# Solar_Batter_Charger_SCH_1.net
KiCad netlist of a schematic drawn in Altium Designer
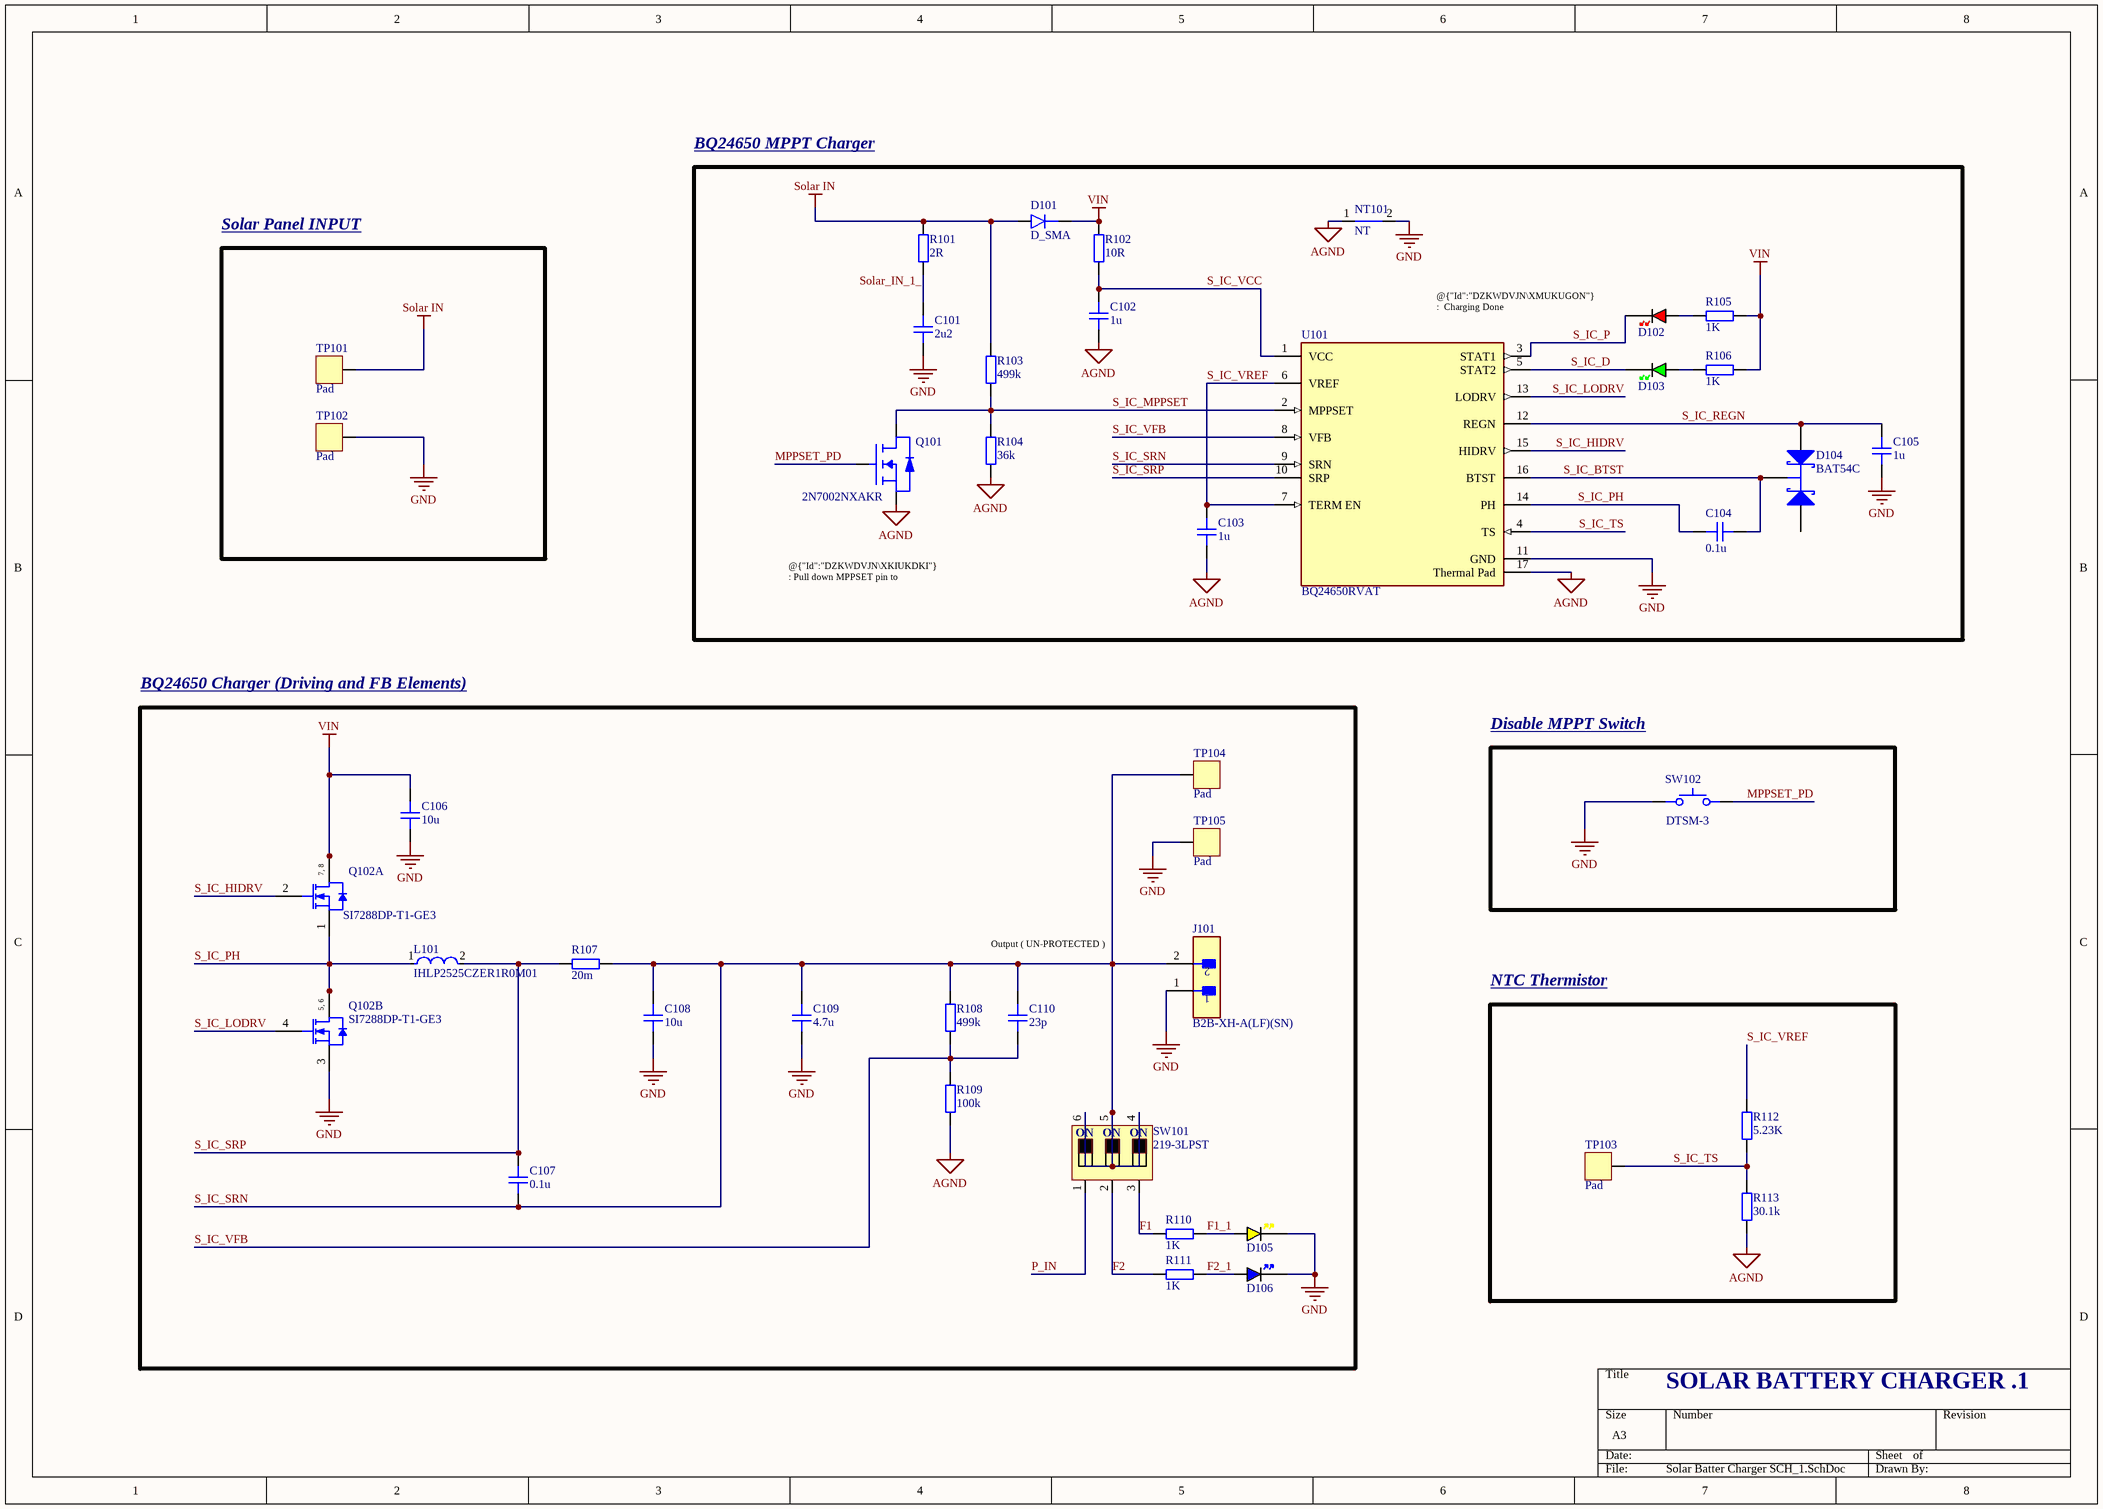
[diagram p0: Solar Batter Charger SCH_1.SchDoc]

(export (version "E")
  (design (tool "Eeschema 10.0.6"))
  (components
    (comp (ref "C101")
      (value "2u2")
      (footprint "CAP_1210")
      (description "Capacitor SMD 1210")
      (libsource (lib "Schematic-Lib-PhilsLab") (part "CAP_1210"))
    )
    (comp (ref "C102")
      (value "1u")
      (footprint "CAP_0805")
      (description "Capacitor SMD 0805")
      (libsource (lib "Schematic-Lib-PhilsLab") (part "CAP_0805"))
    )
    (comp (ref "C103")
      (value "1u")
      (footprint "CAP_0402")
      (description "Capacitor SMD 0402")
      (libsource (lib "Schematic-Lib-PhilsLab") (part "CAP_0402"))
    )
    (comp (ref "C104")
      (value "0.1u")
      (footprint "CAP_0805")
      (description "Capacitor SMD 0805")
      (libsource (lib "Schematic-Lib-PhilsLab") (part "CAP_0805"))
    )
    (comp (ref "C105")
      (value "1u")
      (footprint "CAP_0805")
      (description "Capacitor SMD 0805")
      (libsource (lib "Schematic-Lib-PhilsLab") (part "CAP_0805"))
    )
    (comp (ref "C106")
      (value "10u")
      (footprint "CAP_1210")
      (description "Capacitor SMD 1210")
      (libsource (lib "Schematic-Lib-PhilsLab") (part "CAP_1210"))
    )
    (comp (ref "C107")
      (value "0.1u")
      (footprint "CAP_0805")
      (description "Capacitor SMD 0805")
      (libsource (lib "Schematic-Lib-PhilsLab") (part "CAP_0805"))
    )
    (comp (ref "C108")
      (value "10u")
      (footprint "CAP_1210")
      (description "Capacitor SMD 1210")
      (libsource (lib "Schematic-Lib-PhilsLab") (part "CAP_1210"))
    )
    (comp (ref "C109")
      (value "4.7u")
      (footprint "CAP_1210")
      (description "Capacitor SMD 1210")
      (libsource (lib "Schematic-Lib-PhilsLab") (part "CAP_1210"))
    )
    (comp (ref "C110")
      (value "23p")
      (footprint "CAP_0603")
      (description "Capacitor SMD 0603")
      (libsource (lib "Schematic-Lib-PhilsLab") (part "CAP_0603"))
    )
    (comp (ref "D101")
      (value "D_SMA")
      (footprint "DO-214AC-2 (SMA)")
      (description "Diode SMD SMA (DO-214AA)")
      (libsource (lib "Schematic-Lib-PhilsLab") (part "D_SMA"))
    )
    (comp (ref "D102")
      (value "RED")
      (footprint "LED_0402_RED")
      (description "LED 0402 RED SMD")
      (libsource (lib "Schematic-Lib-PhilsLab") (part "LED_0402_RED"))
    )
    (comp (ref "D103")
      (value "GREEN")
      (footprint "LED_0402_GREEN")
      (description "LED 0402 GREEN SMD")
      (libsource (lib "Schematic-Lib-PhilsLab") (part "LED_0402_GREEN"))
    )
    (comp (ref "D104")
      (value "BAT54C")
      (footprint "NXP-SOT23-3_V")
      (description "Schottky Barrier Diode, 30 V, 2 uA, -55 to 150 degC, 3-Pin SOT23, RoHS, Tape and Reel")
      (fields (field (name "MANUFACTURER") "NXP Semiconductors"))
      (libsource (lib "Altium Content Vault") (part "NXP-DSKY_A1A2K3-3"))
    )
    (comp (ref "D105")
      (value "YELLOW")
      (footprint "LED_0603_YELLOW")
      (description "LED 0603 YELLOW SMD")
      (libsource (lib "Schematic-Lib-PhilsLab") (part "LED_0603_YELLOW"))
    )
    (comp (ref "D106")
      (value "BLUE")
      (footprint "LED_0603_BLUE")
      (description "LED 0603 BLUE SMD")
      (libsource (lib "Schematic-Lib-PhilsLab") (part "LED_0603_BLUE"))
    )
    (comp (ref "J101")
      (value "B2B-XH-A(LF)(SN)")
      (footprint "FP-B2B-XH-A_LF_SN-MFG")
      (description "CONN HEADER VERT 2POS 2.5MM")
      (libsource (lib "Altium Content Vault") (part "3bc925449376181038e59eaffc5286c"))
    )
    (comp (ref "L101")
      (value "IHLP2525CZER1R0M01")
      (footprint "FP-IHLP-2525CZ-FP_2_413x3-MFG")
      (description "Commercial Inductors, High Saturation Series 1uH 11A 10mΩ 20%")
      (fields (field (name "TOLERANCE") "20%"))
      (libsource (lib "Altium Content Vault") (part "725321dda6339637d4d059423bc1c3c"))
    )
    (comp (ref "NT101")
      (value "NT")
      (footprint "NETTIE_SMD")
      (description "Net Tie SMD")
      (libsource (lib "Schematic-Lib-PhilsLab") (part "NetTie_SMD"))
    )
    (comp (ref "Q101")
      (value "2N7002NXAKR")
      (footprint "SSM3J338R,LF-SOT23-F")
      (description "MOSFET N-Channel Vds=60V Id=300mA with ESD Protection")
      (fields (field (name "MANUFACTURER") "Nexperia"))
      (libsource (lib "Schematic-Lib-PhilsLab") (part "2N7002NXAKR"))
    )
    (comp (ref "Q102")
      (value "SI7288DP-T1-GE3")
      (footprint "VISH-POWERPAKSO-8_A_V")
      (description "Dual N-Channel (D-S) MOSFET, 40 V, 20 A, -55 to 150 degC, 8-Pin POWERPAKSO-8, RoHS, Tape and Reel")
      (fields (field (name "MANUFACTURER") "Vishay"))
      (libsource (lib "Altium Content Vault") (part "NEMOS-SGDD-SGDD-8"))
    )
    (comp (ref "R101")
      (value "2R")
      (footprint "RES_1206")
      (description "Resistor SMD 1206")
      (libsource (lib "Schematic-Lib-PhilsLab") (part "RES_1206"))
    )
    (comp (ref "R102")
      (value "10R")
      (footprint "RES_1206")
      (description "Resistor SMD 1206")
      (libsource (lib "Schematic-Lib-PhilsLab") (part "RES_1206"))
    )
    (comp (ref "R103")
      (value "499k")
      (footprint "RES_0402")
      (description "Resistor SMD 0402")
      (libsource (lib "Schematic-Lib-PhilsLab") (part "RES_0402"))
    )
    (comp (ref "R104")
      (value "36k")
      (footprint "RES_0402")
      (description "Resistor SMD 0402")
      (libsource (lib "Schematic-Lib-PhilsLab") (part "RES_0402"))
    )
    (comp (ref "R105")
      (value "1K")
      (footprint "RES_0402")
      (description "Resistor SMD 0402")
      (libsource (lib "Schematic-Lib-PhilsLab") (part "RES_0402"))
    )
    (comp (ref "R106")
      (value "1K")
      (footprint "RES_0402")
      (description "Resistor SMD 0402")
      (libsource (lib "Schematic-Lib-PhilsLab") (part "RES_0402"))
    )
    (comp (ref "R107")
      (value "20m")
      (footprint "RES_1206")
      (description "Resistor SMD 1206")
      (libsource (lib "Schematic-Lib-PhilsLab") (part "RES_1206"))
    )
    (comp (ref "R108")
      (value "499k")
      (footprint "RES_0402")
      (description "Resistor SMD 0402")
      (libsource (lib "Schematic-Lib-PhilsLab") (part "RES_0402"))
    )
    (comp (ref "R109")
      (value "100k")
      (footprint "RES_0402")
      (description "Resistor SMD 0402")
      (libsource (lib "Schematic-Lib-PhilsLab") (part "RES_0402"))
    )
    (comp (ref "R110")
      (value "1K")
      (footprint "RES_0402")
      (description "Resistor SMD 0402")
      (libsource (lib "Schematic-Lib-PhilsLab") (part "RES_0402"))
    )
    (comp (ref "R111")
      (value "1K")
      (footprint "RES_0402")
      (description "Resistor SMD 0402")
      (libsource (lib "Schematic-Lib-PhilsLab") (part "RES_0402"))
    )
    (comp (ref "R112")
      (value "5.23K")
      (footprint "RES_0402")
      (description "Resistor SMD 0402")
      (libsource (lib "Schematic-Lib-PhilsLab") (part "RES_0402"))
    )
    (comp (ref "R113")
      (value "30.1k")
      (footprint "RES_0402")
      (description "Resistor SMD 0402")
      (libsource (lib "Schematic-Lib-PhilsLab") (part "RES_0402"))
    )
    (comp (ref "SW101")
      (value "219-3LPST")
      (footprint "219-3LPST")
      (description "DIP Switches SPST 3x")
      (fields (field (name "MANUFACTURER") "CTS"))
      (libsource (lib "Schematic-Lib-PhilsLab") (part "219-3LPST"))
    )
    (comp (ref "SW102")
      (value "DTSM-3")
      (footprint "DTSM-3")
      (description "Tactile Switch SMD SPST")
      (fields (field (name "MANUFACTURER") "Diptronics"))
      (libsource (lib "Schematic-Lib-PhilsLab") (part "DTSM-3"))
    )
    (comp (ref "TP101")
      (value "Pad")
      (footprint "PAD_SQ_2MM")
      (description "Test Point Square 2mm")
      (libsource (lib "") (part "PAD_SQ_2MM_1"))
    )
    (comp (ref "TP102")
      (value "Pad")
      (footprint "PAD_SQ_2MM")
      (description "Test Point Square 2mm")
      (libsource (lib "") (part "PAD_SQ_2MM_1"))
    )
    (comp (ref "TP103")
      (value "Pad")
      (footprint "PAD_SQ_2MM")
      (description "Test Point Square 2mm")
      (libsource (lib "") (part "PAD_SQ_2MM_1"))
    )
    (comp (ref "TP104")
      (value "Pad")
      (footprint "PAD_SQ_2MM")
      (description "Test Point Square 2mm")
      (libsource (lib "Schematic-Lib-PhilsLab") (part "PAD_SQ_2MM"))
    )
    (comp (ref "TP105")
      (value "Pad")
      (footprint "PAD_SQ_2MM")
      (description "Test Point Square 2mm")
      (libsource (lib "Schematic-Lib-PhilsLab") (part "PAD_SQ_2MM"))
    )
    (comp (ref "U101")
      (value "BQ24650RVAT")
      (footprint "FP-RVA0016A-MFG")
      (description "IC SYNC SW-MODE BAT CHRGR 16VQFN")
      (libsource (lib "Altium Content Vault") (part "cf19bb46e92d87c2bf2948a47118a18"))
    )
  )
  (nets
    (net (code "1") (name "/F1") (class "Default")
      (node (ref "R110") (pin "2") (pinfunction "2_2") (pintype "passive"))
      (node (ref "SW101") (pin "3") (pinfunction "3_3") (pintype "passive"))
    )
    (net (code "2") (name "/F1_1") (class "Default")
      (node (ref "D105") (pin "A") (pinfunction "A_A") (pintype "passive"))
      (node (ref "R110") (pin "1") (pinfunction "1_1") (pintype "passive"))
    )
    (net (code "3") (name "/F2") (class "Default")
      (node (ref "R111") (pin "2") (pinfunction "2_2") (pintype "passive"))
      (node (ref "SW101") (pin "2") (pinfunction "2_2") (pintype "passive"))
    )
    (net (code "4") (name "/F2_1") (class "Default")
      (node (ref "D106") (pin "A") (pinfunction "A_A") (pintype "passive"))
      (node (ref "R111") (pin "1") (pinfunction "1_1") (pintype "passive"))
    )
    (net (code "5") (name "/MPPSET_PD") (class "Default")
      (node (ref "Q101") (pin "G") (pinfunction "G_G") (pintype "passive"))
      (node (ref "SW102") (pin "2") (pintype "passive"))
    )
    (net (code "6") (name "/P_IN") (class "Default")
      (node (ref "SW101") (pin "1") (pinfunction "1_1") (pintype "passive"))
    )
    (net (code "7") (name "/S_IC_BTST") (class "Default")
      (node (ref "C104") (pin "1") (pinfunction "1_1") (pintype "passive"))
      (node (ref "D104") (pin "3") (pinfunction "K_3") (pintype "passive"))
      (node (ref "U101") (pin "16") (pinfunction "BTST_16") (pintype "power_in"))
    )
    (net (code "8") (name "/S_IC_D") (class "Default")
      (node (ref "D103") (pin "K") (pinfunction "K_K") (pintype "passive"))
      (node (ref "U101") (pin "5") (pinfunction "STAT2_5") (pintype "output"))
    )
    (net (code "9") (name "/S_IC_HIDRV") (class "Default")
      (node (ref "Q102") (pin "2") (pinfunction "G1_2") (pintype "passive"))
      (node (ref "U101") (pin "15") (pinfunction "HIDRV_15") (pintype "output"))
    )
    (net (code "10") (name "/S_IC_LODRV") (class "Default")
      (node (ref "Q102") (pin "4") (pinfunction "G2_4") (pintype "passive"))
      (node (ref "U101") (pin "13") (pinfunction "LODRV_13") (pintype "output"))
    )
    (net (code "11") (name "/S_IC_MPPSET") (class "Default")
      (node (ref "Q101") (pin "D") (pinfunction "D_D") (pintype "passive"))
      (node (ref "R103") (pin "1") (pinfunction "1_1") (pintype "passive"))
      (node (ref "R104") (pin "2") (pinfunction "2_2") (pintype "passive"))
      (node (ref "U101") (pin "2") (pinfunction "MPPSET_2") (pintype "input"))
    )
    (net (code "12") (name "/S_IC_P") (class "Default")
      (node (ref "D102") (pin "K") (pinfunction "K_K") (pintype "passive"))
      (node (ref "U101") (pin "3") (pinfunction "STAT1_3") (pintype "output"))
    )
    (net (code "13") (name "/S_IC_PH") (class "Default")
      (node (ref "C104") (pin "2") (pinfunction "2_2") (pintype "passive"))
      (node (ref "L101") (pin "1") (pinfunction "1_1") (pintype "passive"))
      (node (ref "Q102") (pin "1") (pinfunction "S1_1") (pintype "passive"))
      (node (ref "Q102") (pin "5") (pinfunction "D2_5") (pintype "passive"))
      (node (ref "Q102") (pin "6") (pinfunction "D2_6") (pintype "passive"))
      (node (ref "U101") (pin "14") (pinfunction "PH_14") (pintype "power_in"))
    )
    (net (code "14") (name "/S_IC_REGN") (class "Default")
      (node (ref "C105") (pin "2") (pinfunction "2_2") (pintype "passive"))
      (node (ref "D104") (pin "2") (pinfunction "A_2") (pintype "passive"))
      (node (ref "U101") (pin "12") (pinfunction "REGN_12") (pintype "power_in"))
    )
    (net (code "15") (name "/S_IC_SRN") (class "Default")
      (node (ref "C107") (pin "2") (pinfunction "2_2") (pintype "passive"))
      (node (ref "C108") (pin "2") (pinfunction "2_2") (pintype "passive"))
      (node (ref "C109") (pin "2") (pinfunction "2_2") (pintype "passive"))
      (node (ref "C110") (pin "2") (pinfunction "2_2") (pintype "passive"))
      (node (ref "J101") (pin "2") (pinfunction "2_2") (pintype "passive"))
      (node (ref "R107") (pin "2") (pinfunction "2_2") (pintype "passive"))
      (node (ref "R108") (pin "2") (pinfunction "2_2") (pintype "passive"))
      (node (ref "SW101") (pin "4") (pinfunction "4_4") (pintype "passive"))
      (node (ref "SW101") (pin "5") (pinfunction "5_5") (pintype "passive"))
      (node (ref "SW101") (pin "6") (pinfunction "6_6") (pintype "passive"))
      (node (ref "TP104") (pin "1") (pinfunction "1_1") (pintype "passive"))
      (node (ref "U101") (pin "9") (pinfunction "SRN_9") (pintype "input"))
    )
    (net (code "16") (name "/S_IC_SRP") (class "Default")
      (node (ref "C107") (pin "1") (pinfunction "1_1") (pintype "passive"))
      (node (ref "L101") (pin "2") (pinfunction "2_2") (pintype "passive"))
      (node (ref "R107") (pin "1") (pinfunction "1_1") (pintype "passive"))
      (node (ref "U101") (pin "10") (pinfunction "SRP_10") (pintype "passive"))
    )
    (net (code "17") (name "/S_IC_TS") (class "Default")
      (node (ref "R112") (pin "1") (pinfunction "1_1") (pintype "passive"))
      (node (ref "R113") (pin "2") (pinfunction "2_2") (pintype "passive"))
      (node (ref "TP103") (pin "1") (pinfunction "1_1") (pintype "passive"))
      (node (ref "U101") (pin "4") (pinfunction "TS_4") (pintype "input"))
    )
    (net (code "18") (name "/S_IC_VCC") (class "Default")
      (node (ref "C102") (pin "2") (pinfunction "2_2") (pintype "passive"))
      (node (ref "R102") (pin "1") (pinfunction "1_1") (pintype "passive"))
      (node (ref "U101") (pin "1") (pinfunction "VCC_1") (pintype "power_in"))
    )
    (net (code "19") (name "/S_IC_VFB") (class "Default")
      (node (ref "C110") (pin "1") (pinfunction "1_1") (pintype "passive"))
      (node (ref "R108") (pin "1") (pinfunction "1_1") (pintype "passive"))
      (node (ref "R109") (pin "2") (pinfunction "2_2") (pintype "passive"))
      (node (ref "U101") (pin "8") (pinfunction "VFB_8") (pintype "input"))
    )
    (net (code "20") (name "/S_IC_VREF") (class "Default")
      (node (ref "C103") (pin "2") (pinfunction "2_2") (pintype "passive"))
      (node (ref "R112") (pin "2") (pinfunction "2_2") (pintype "passive"))
      (node (ref "U101") (pin "6") (pinfunction "VREF_6") (pintype "power_in"))
      (node (ref "U101") (pin "7") (pinfunction "TERM_EN_7") (pintype "input"))
    )
    (net (code "21") (name "/Solar_IN_1_") (class "Default")
      (node (ref "C101") (pin "2") (pinfunction "2_2") (pintype "passive"))
      (node (ref "R101") (pin "1") (pinfunction "1_1") (pintype "passive"))
    )
    (net (code "22") (name "AGND") (class "Default")
      (node (ref "C102") (pin "1") (pinfunction "1_1") (pintype "passive"))
      (node (ref "C103") (pin "1") (pinfunction "1_1") (pintype "passive"))
      (node (ref "NT101") (pin "1") (pinfunction "1_1") (pintype "passive"))
      (node (ref "Q101") (pin "S") (pinfunction "S_S") (pintype "passive"))
      (node (ref "R104") (pin "1") (pinfunction "1_1") (pintype "passive"))
      (node (ref "R109") (pin "1") (pinfunction "1_1") (pintype "passive"))
      (node (ref "R113") (pin "1") (pinfunction "1_1") (pintype "passive"))
      (node (ref "U101") (pin "17") (pinfunction "Thermal_Pad_17") (pintype "power_in"))
    )
    (net (code "23") (name "GND") (class "Default")
      (node (ref "C101") (pin "1") (pinfunction "1_1") (pintype "passive"))
      (node (ref "C105") (pin "1") (pinfunction "1_1") (pintype "passive"))
      (node (ref "C106") (pin "1") (pinfunction "1_1") (pintype "passive"))
      (node (ref "C108") (pin "1") (pinfunction "1_1") (pintype "passive"))
      (node (ref "C109") (pin "1") (pinfunction "1_1") (pintype "passive"))
      (node (ref "D105") (pin "K") (pinfunction "K_K") (pintype "passive"))
      (node (ref "D106") (pin "K") (pinfunction "K_K") (pintype "passive"))
      (node (ref "J101") (pin "1") (pinfunction "1_1") (pintype "passive"))
      (node (ref "NT101") (pin "2") (pinfunction "2_2") (pintype "passive"))
      (node (ref "Q102") (pin "3") (pinfunction "S2_3") (pintype "passive"))
      (node (ref "SW102") (pin "1") (pintype "passive"))
      (node (ref "TP102") (pin "1") (pinfunction "1_1") (pintype "passive"))
      (node (ref "TP105") (pin "1") (pinfunction "1_1") (pintype "passive"))
      (node (ref "U101") (pin "11") (pinfunction "GND_11") (pintype "power_in"))
    )
    (net (code "24") (name "Net-(D102-PadA)") (class "Default")
      (node (ref "D102") (pin "A") (pinfunction "A_A") (pintype "passive"))
      (node (ref "R105") (pin "1") (pinfunction "1_1") (pintype "passive"))
    )
    (net (code "25") (name "Net-(D103-PadA)") (class "Default")
      (node (ref "D103") (pin "A") (pinfunction "A_A") (pintype "passive"))
      (node (ref "R106") (pin "1") (pinfunction "1_1") (pintype "passive"))
    )
    (net (code "26") (name "Solar IN") (class "Default")
      (node (ref "D101") (pin "A") (pinfunction "A_A") (pintype "passive"))
      (node (ref "R101") (pin "2") (pinfunction "2_2") (pintype "passive"))
      (node (ref "R103") (pin "2") (pinfunction "2_2") (pintype "passive"))
      (node (ref "TP101") (pin "1") (pinfunction "1_1") (pintype "passive"))
    )
    (net (code "27") (name "VIN") (class "Default")
      (node (ref "C106") (pin "2") (pinfunction "2_2") (pintype "passive"))
      (node (ref "D101") (pin "K") (pinfunction "K_K") (pintype "passive"))
      (node (ref "Q102") (pin "7") (pinfunction "D1_7") (pintype "passive"))
      (node (ref "Q102") (pin "8") (pinfunction "D1_8") (pintype "passive"))
      (node (ref "R102") (pin "2") (pinfunction "2_2") (pintype "passive"))
      (node (ref "R105") (pin "2") (pinfunction "2_2") (pintype "passive"))
      (node (ref "R106") (pin "2") (pinfunction "2_2") (pintype "passive"))
    )
    (net (code "28") (name "unconnected-(D104-A-Pad1)") (class "Default")
      (node (ref "D104") (pin "1") (pinfunction "A_1") (pintype "passive"))
    )
  )
)
